# 1_8V.net
KiCad netlist of a schematic drawn in Altium Designer
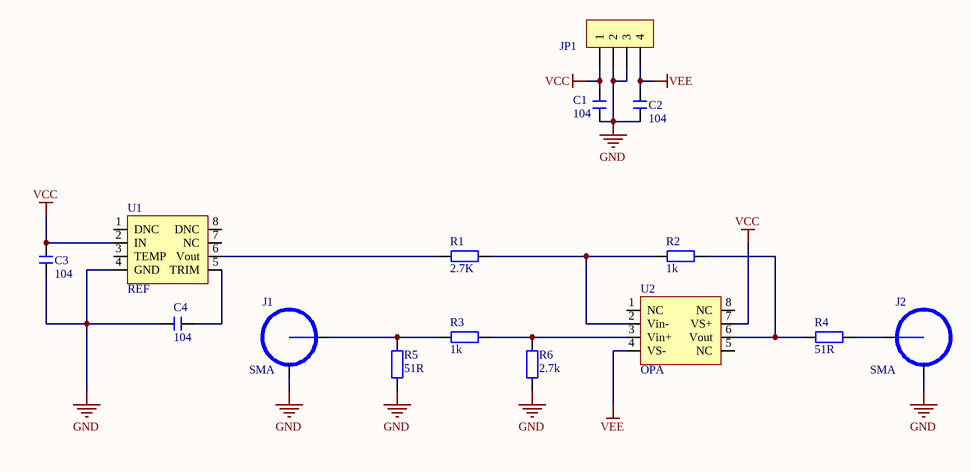
[diagram p0: 拉低1.8V.SchDoc]

(export (version "E")
  (design (tool "Eeschema 10.0.6"))
  (components
    (comp (ref "C1")
      (value "104")
      (footprint "C 0805_L")
      (description "无极性贴片电容")
      (fields (field (name "版权归属") "源创客"))
      (libsource (lib "3.1   - 电阻-电容-电感") (part "C"))
    )
    (comp (ref "C2")
      (value "104")
      (footprint "C 0805_L")
      (description "无极性贴片电容")
      (fields (field (name "版权归属") "源创客"))
      (libsource (lib "3.1   - 电阻-电容-电感") (part "C"))
    )
    (comp (ref "C3")
      (value "104")
      (footprint "C 0805_L")
      (description "无极性贴片电容")
      (fields (field (name "版权归属") "源创客"))
      (libsource (lib "3.1   - 电阻-电容-电感") (part "C"))
    )
    (comp (ref "C4")
      (value "104")
      (footprint "C 0805_L")
      (description "无极性贴片电容")
      (fields (field (name "版权归属") "源创客"))
      (libsource (lib "3.1   - 电阻-电容-电感") (part "C"))
    )
    (comp (ref "J1") (value "SMA") (footprint "HDR2.54-LI-2P") (libsource (lib "") (part "SMA_1")))
    (comp (ref "J2") (value "SMA") (footprint "HDR2.54-LI-2P") (libsource (lib "电子竞赛") (part "SMA")))
    (comp (ref "JP1")
      (value "HDR-1X4")
      (footprint "KF2510-LI-4P")
      (description "4P接插件")
      (fields (field (name "版权归属") "源创客"))
      (libsource (lib "4.5   - 接插件-脚距2.54") (part "Header 4"))
    )
    (comp (ref "R1")
      (value "2.7K")
      (footprint "R 0805_L")
      (description "贴片电阻")
      (fields (field (name "版权归属") "源创客"))
      (libsource (lib "3.1   - 电阻-电容-电感") (part "R"))
    )
    (comp (ref "R2")
      (value "1k")
      (footprint "R 0805_L")
      (description "贴片电阻")
      (fields (field (name "版权归属") "源创客"))
      (libsource (lib "3.1   - 电阻-电容-电感") (part "R"))
    )
    (comp (ref "R3")
      (value "1k")
      (footprint "R 0805_L")
      (description "贴片电阻")
      (fields (field (name "版权归属") "源创客"))
      (libsource (lib "3.1   - 电阻-电容-电感") (part "R"))
    )
    (comp (ref "R4")
      (value "51R")
      (footprint "R 0805_L")
      (description "贴片电阻")
      (fields (field (name "版权归属") "源创客"))
      (libsource (lib "3.1   - 电阻-电容-电感") (part "R"))
    )
    (comp (ref "R5")
      (value "51R")
      (footprint "R 0805_L")
      (description "贴片电阻")
      (fields (field (name "版权归属") "源创客"))
      (libsource (lib "3.1   - 电阻-电容-电感") (part "R"))
    )
    (comp (ref "R6")
      (value "2.7k")
      (footprint "R 0805_L")
      (description "贴片电阻")
      (fields (field (name "版权归属") "源创客"))
      (libsource (lib "3.1   - 电阻-电容-电感") (part "R"))
    )
    (comp (ref "U1") (value "REF") (footprint "SOP8_M") (libsource (lib "电子竞赛") (part "单运放")))
    (comp (ref "U2") (value "OPA") (footprint "SOP8_M") (libsource (lib "电子竞赛") (part "单运放")))
  )
  (nets
    (net (code "1") (name "GND") (class "Default")
      (node (ref "C1") (pin "1") (pinfunction "1_1") (pintype "passive"))
      (node (ref "C2") (pin "1") (pinfunction "1_1") (pintype "passive"))
      (node (ref "C3") (pin "1") (pinfunction "1_1") (pintype "passive"))
      (node (ref "C4") (pin "2") (pinfunction "2_2") (pintype "passive"))
      (node (ref "J1") (pin "2") (pinfunction "2_2") (pintype "passive"))
      (node (ref "J2") (pin "2") (pinfunction "2_2") (pintype "passive"))
      (node (ref "JP1") (pin "2") (pinfunction "2_2") (pintype "passive"))
      (node (ref "JP1") (pin "3") (pinfunction "3_3") (pintype "passive"))
      (node (ref "R5") (pin "1") (pinfunction "1_1") (pintype "passive"))
      (node (ref "R6") (pin "1") (pinfunction "1_1") (pintype "passive"))
      (node (ref "U1") (pin "4") (pinfunction "GND_4") (pintype "passive"))
    )
    (net (code "2") (name "Net-(J1-Pad1)") (class "Default")
      (node (ref "J1") (pin "1") (pinfunction "1_1") (pintype "passive"))
      (node (ref "R3") (pin "1") (pinfunction "1_1") (pintype "passive"))
      (node (ref "R5") (pin "2") (pinfunction "2_2") (pintype "passive"))
    )
    (net (code "3") (name "Net-(J2-Pad1)") (class "Default")
      (node (ref "J2") (pin "1") (pinfunction "1_1") (pintype "passive"))
      (node (ref "R4") (pin "2") (pinfunction "2_2") (pintype "passive"))
    )
    (net (code "4") (name "Net-(U1-TRIM)") (class "Default")
      (node (ref "C4") (pin "1") (pinfunction "1_1") (pintype "passive"))
      (node (ref "U1") (pin "5") (pinfunction "TRIM_5") (pintype "passive"))
    )
    (net (code "5") (name "Net-(U1-Vout)") (class "Default")
      (node (ref "R1") (pin "1") (pinfunction "1_1") (pintype "passive"))
      (node (ref "U1") (pin "6") (pinfunction "Vout_6") (pintype "passive"))
    )
    (net (code "6") (name "Net-(U2-IN)") (class "Default")
      (node (ref "R1") (pin "2") (pinfunction "2_2") (pintype "passive"))
      (node (ref "R2") (pin "1") (pinfunction "1_1") (pintype "passive"))
      (node (ref "U2") (pin "2") (pinfunction "IN_2") (pintype "passive"))
    )
    (net (code "7") (name "Net-(U2-TEMP)") (class "Default")
      (node (ref "R3") (pin "2") (pinfunction "2_2") (pintype "passive"))
      (node (ref "R6") (pin "2") (pinfunction "2_2") (pintype "passive"))
      (node (ref "U2") (pin "3") (pinfunction "TEMP_3") (pintype "passive"))
    )
    (net (code "8") (name "Net-(U2-Vout)") (class "Default")
      (node (ref "R2") (pin "2") (pinfunction "2_2") (pintype "passive"))
      (node (ref "R4") (pin "1") (pinfunction "1_1") (pintype "passive"))
      (node (ref "U2") (pin "6") (pinfunction "Vout_6") (pintype "passive"))
    )
    (net (code "9") (name "VCC") (class "Default")
      (node (ref "C1") (pin "2") (pinfunction "2_2") (pintype "passive"))
      (node (ref "C3") (pin "2") (pinfunction "2_2") (pintype "passive"))
      (node (ref "JP1") (pin "1") (pinfunction "1_1") (pintype "passive"))
      (node (ref "U1") (pin "2") (pinfunction "IN_2") (pintype "passive"))
      (node (ref "U2") (pin "7") (pinfunction "NC_7") (pintype "passive"))
    )
    (net (code "10") (name "VEE") (class "Default")
      (node (ref "C2") (pin "2") (pinfunction "2_2") (pintype "passive"))
      (node (ref "JP1") (pin "4") (pinfunction "4_4") (pintype "passive"))
      (node (ref "U2") (pin "4") (pinfunction "GND_4") (pintype "passive"))
    )
    (net (code "11") (name "unconnected-(U1-DNC-Pad1)") (class "Default")
      (node (ref "U1") (pin "1") (pinfunction "DNC_1") (pintype "passive"))
    )
    (net (code "12") (name "unconnected-(U1-DNC-Pad8)") (class "Default")
      (node (ref "U1") (pin "8") (pinfunction "DNC_8") (pintype "passive"))
    )
    (net (code "13") (name "unconnected-(U1-NC-Pad7)") (class "Default")
      (node (ref "U1") (pin "7") (pinfunction "NC_7") (pintype "passive"))
    )
    (net (code "14") (name "unconnected-(U1-TEMP-Pad3)") (class "Default")
      (node (ref "U1") (pin "3") (pinfunction "TEMP_3") (pintype "passive"))
    )
    (net (code "15") (name "unconnected-(U2-DNC-Pad1)") (class "Default")
      (node (ref "U2") (pin "1") (pinfunction "DNC_1") (pintype "passive"))
    )
    (net (code "16") (name "unconnected-(U2-DNC-Pad8)") (class "Default")
      (node (ref "U2") (pin "8") (pinfunction "DNC_8") (pintype "passive"))
    )
    (net (code "17") (name "unconnected-(U2-TRIM-Pad5)") (class "Default")
      (node (ref "U2") (pin "5") (pinfunction "TRIM_5") (pintype "passive"))
    )
  )
)
